# NNLightSwitcher_analog.net
KiCad netlist of a schematic drawn in Altium Designer
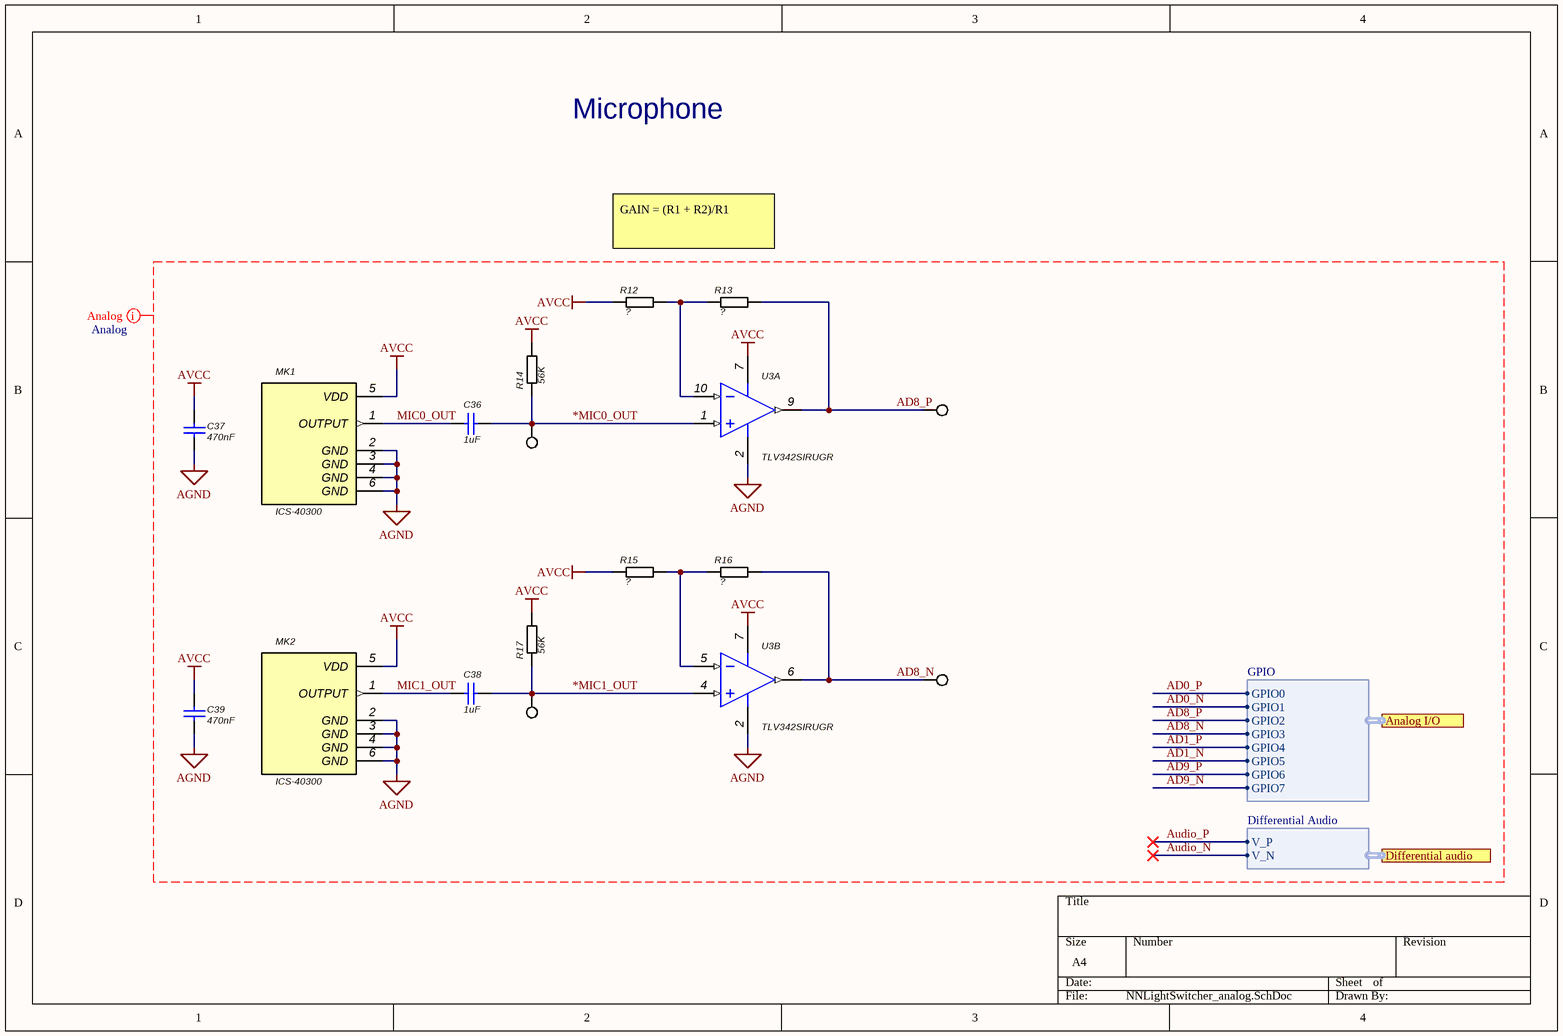
[diagram p0: NNLightSwitcher_analog.SchDoc]

(export (version "E")
  (design (tool "Eeschema 10.0.6"))
  (components
    (comp (ref "C36")
      (value "1uF")
      (footprint "0402")
      (libsource (lib "NNLightSwitcher") (part "Capacitor 1uF"))
    )
    (comp (ref "C37")
      (value "470nF")
      (footprint "0402")
      (libsource (lib "NNLightSwitcher") (part "Capacitor 470nF"))
    )
    (comp (ref "C38")
      (value "1uF")
      (footprint "0402")
      (libsource (lib "NNLightSwitcher") (part "Capacitor 1uF"))
    )
    (comp (ref "C39")
      (value "470nF")
      (footprint "0402")
      (libsource (lib "NNLightSwitcher") (part "Capacitor 470nF"))
    )
    (comp (ref "MK1")
      (value "ICS-40300")
      (footprint "*MIC_ICS-40300")
      (description "High SPL Analog MEMS Microphone with Extended Low Feq Response")
      (libsource (lib "NNLightSwitcher") (part "ICS-40300"))
    )
    (comp (ref "MK2")
      (value "ICS-40300")
      (footprint "*MIC_ICS-40300")
      (description "High SPL Analog MEMS Microphone with Extended Low Feq Response")
      (libsource (lib "NNLightSwitcher") (part "ICS-40300"))
    )
    (comp (ref "R12")
      (value "?")
      (footprint "0402")
      (libsource (lib "NNLightSwitcher") (part "Resistor generic"))
    )
    (comp (ref "R13")
      (value "?")
      (footprint "0402")
      (libsource (lib "NNLightSwitcher") (part "Resistor generic"))
    )
    (comp (ref "R14")
      (value "56K")
      (footprint "0402")
      (libsource (lib "NNLightSwitcher") (part "Resistor 56K"))
    )
    (comp (ref "R15")
      (value "?")
      (footprint "0402")
      (libsource (lib "NNLightSwitcher") (part "Resistor generic"))
    )
    (comp (ref "R16")
      (value "?")
      (footprint "0402")
      (libsource (lib "NNLightSwitcher") (part "Resistor generic"))
    )
    (comp (ref "R17")
      (value "56K")
      (footprint "0402")
      (libsource (lib "NNLightSwitcher") (part "Resistor 56K"))
    )
    (comp (ref "TP3")
      (value "Test point")
      (footprint "Testpoint_with_pad")
      (description "Test Point, Miniature, SMT")
      (libsource (lib "NNLightSwitcher") (part "Test point"))
    )
    (comp (ref "TP4")
      (value "Test point")
      (footprint "Testpoint_with_pad")
      (description "Test Point, Miniature, SMT")
      (libsource (lib "NNLightSwitcher") (part "Test point"))
    )
    (comp (ref "TP5")
      (value "Test point")
      (footprint "Testpoint_with_pad")
      (description "Test Point, Miniature, SMT")
      (libsource (lib "NNLightSwitcher") (part "Test point"))
    )
    (comp (ref "TP6")
      (value "Test point")
      (footprint "Testpoint_with_pad")
      (description "Test Point, Miniature, SMT")
      (libsource (lib "NNLightSwitcher") (part "Test point"))
    )
    (comp (ref "U3")
      (value "TLV342SIRUGR")
      (footprint "TI-RUG10_V")
      (libsource (lib "NNLightSwitcher") (part "TLV342SIRUGR"))
    )
  )
  (nets
    (net (code "4") (name "/*MIC0_OUT") (class "Default")
      (node (ref "C36") (pin "1") (pinfunction "1_1") (pintype "passive"))
      (node (ref "R14") (pin "1") (pinfunction "1_1") (pintype "passive"))
      (node (ref "TP4") (pin "1") (pintype "passive"))
      (node (ref "U3") (pin "1") (pinfunction "IN1+_1") (pintype "input"))
    )
    (net (code "5") (name "/*MIC1_OUT") (class "Default")
      (node (ref "C38") (pin "1") (pinfunction "1_1") (pintype "passive"))
      (node (ref "R17") (pin "1") (pinfunction "1_1") (pintype "passive"))
      (node (ref "TP6") (pin "1") (pintype "passive"))
      (node (ref "U3") (pin "4") (pinfunction "IN2+_4") (pintype "input"))
    )
    (net (code "10") (name "/AD8_N") (class "Default")
      (node (ref "R16") (pin "2") (pinfunction "2_2") (pintype "passive"))
      (node (ref "TP5") (pin "1") (pintype "passive"))
      (node (ref "U3") (pin "6") (pinfunction "OUT2_6") (pintype "output"))
    )
    (net (code "11") (name "/AD8_P") (class "Default")
      (node (ref "R13") (pin "2") (pinfunction "2_2") (pintype "passive"))
      (node (ref "TP3") (pin "1") (pintype "passive"))
      (node (ref "U3") (pin "9") (pinfunction "OUT1_9") (pintype "output"))
    )
    (net (code "16") (name "/MIC0_OUT") (class "Default")
      (node (ref "C36") (pin "2") (pinfunction "2_2") (pintype "passive"))
      (node (ref "MK1") (pin "1") (pinfunction "OUTPUT_1") (pintype "output"))
    )
    (net (code "17") (name "/MIC1_OUT") (class "Default")
      (node (ref "C38") (pin "2") (pinfunction "2_2") (pintype "passive"))
      (node (ref "MK2") (pin "1") (pinfunction "OUTPUT_1") (pintype "output"))
    )
    (net (code "20") (name "AGND") (class "Default")
      (node (ref "C37") (pin "2") (pinfunction "2_2") (pintype "passive"))
      (node (ref "C39") (pin "2") (pinfunction "2_2") (pintype "passive"))
      (node (ref "MK1") (pin "2") (pinfunction "GND_2") (pintype "power_in"))
      (node (ref "MK1") (pin "3") (pinfunction "GND_3") (pintype "power_in"))
      (node (ref "MK1") (pin "4") (pinfunction "GND_4") (pintype "power_in"))
      (node (ref "MK1") (pin "6") (pinfunction "GND_6") (pintype "power_in"))
      (node (ref "MK2") (pin "2") (pinfunction "GND_2") (pintype "power_in"))
      (node (ref "MK2") (pin "3") (pinfunction "GND_3") (pintype "power_in"))
      (node (ref "MK2") (pin "4") (pinfunction "GND_4") (pintype "power_in"))
      (node (ref "MK2") (pin "6") (pinfunction "GND_6") (pintype "power_in"))
      (node (ref "U3") (pin "2") (pinfunction "GND_2") (pintype "power_in"))
    )
    (net (code "21") (name "AVCC") (class "Default")
      (node (ref "C37") (pin "1") (pinfunction "1_1") (pintype "passive"))
      (node (ref "C39") (pin "1") (pinfunction "1_1") (pintype "passive"))
      (node (ref "MK1") (pin "5") (pinfunction "VDD_5") (pintype "power_in"))
      (node (ref "MK2") (pin "5") (pinfunction "VDD_5") (pintype "power_in"))
      (node (ref "R12") (pin "1") (pinfunction "1_1") (pintype "passive"))
      (node (ref "R14") (pin "2") (pinfunction "2_2") (pintype "passive"))
      (node (ref "R15") (pin "1") (pinfunction "1_1") (pintype "passive"))
      (node (ref "R17") (pin "2") (pinfunction "2_2") (pintype "passive"))
      (node (ref "U3") (pin "7") (pinfunction "V+_7") (pintype "power_in"))
    )
    (net (code "22") (name "Net-(U3A-IN1-)") (class "Default")
      (node (ref "R12") (pin "2") (pinfunction "2_2") (pintype "passive"))
      (node (ref "R13") (pin "1") (pinfunction "1_1") (pintype "passive"))
      (node (ref "U3") (pin "10") (pinfunction "IN1-_10") (pintype "input"))
    )
    (net (code "23") (name "Net-(U3B-IN2-)") (class "Default")
      (node (ref "R15") (pin "2") (pinfunction "2_2") (pintype "passive"))
      (node (ref "R16") (pin "1") (pinfunction "1_1") (pintype "passive"))
      (node (ref "U3") (pin "5") (pinfunction "IN2-_5") (pintype "input"))
    )
  )
)
